# rl78l1a_smart_blood_pressure_monitor_sch.net
KiCad netlist of a schematic drawn in Altium Designer
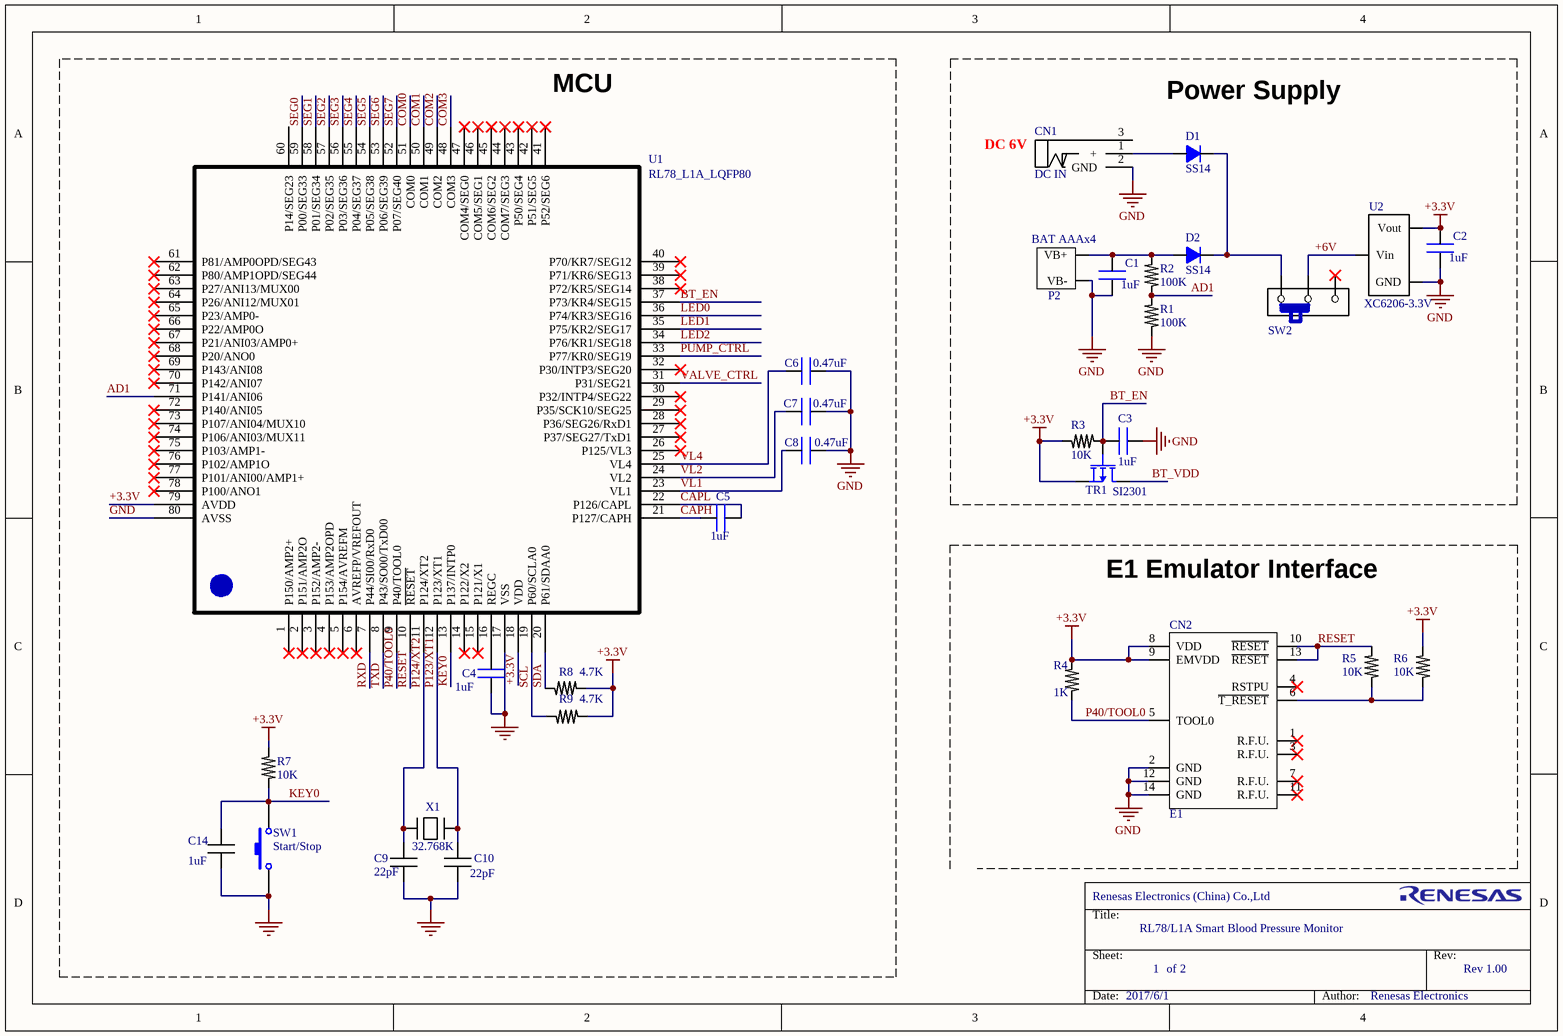
[diagram p0: rl78l1a_smart_blood_pressure_monitor_sch1.SchDoc]

(export (version "E")
  (design (tool "Eeschema 10.0.6"))
  (components
    (comp (ref "C1") (value "1uF") (footprint "0603") (libsource (lib "分立元件") (part "CAP")))
    (comp (ref "C2") (value "1uF") (footprint "0603") (libsource (lib "分立元件") (part "CAP")))
    (comp (ref "C3") (value "1uF") (footprint "0603") (libsource (lib "分立元件") (part "CAP")))
    (comp (ref "C4") (value "1uF") (footprint "0603") (libsource (lib "分立元件") (part "CAP")))
    (comp (ref "C5") (value "1uF") (footprint "0805") (libsource (lib "分立元件") (part "CAP")))
    (comp (ref "C6") (value "0.47uF") (footprint "0805") (libsource (lib "分立元件") (part "CAP")))
    (comp (ref "C7") (value "0.47uF") (footprint "0805") (libsource (lib "分立元件") (part "CAP")))
    (comp (ref "C8") (value "0.47uF") (footprint "0805") (libsource (lib "分立元件") (part "CAP")))
    (comp (ref "C9") (value "22pF") (footprint "0805") (libsource (lib "*") (part "CAP")))
    (comp (ref "C10") (value "22pF") (footprint "0805") (libsource (lib "*") (part "CAP")))
    (comp (ref "C14") (value "1uF") (footprint "0603") (libsource (lib "*") (part "CAP")))
    (comp (ref "CN1") (value "DC IN") (footprint "POWER IN A") (libsource (lib "*") (part "DC IN")))
    (comp (ref "D1") (value "SS14") (footprint "D1N") (libsource (lib "分立元件") (part "1SS404")))
    (comp (ref "D2") (value "SS14") (footprint "D1N") (libsource (lib "分立元件") (part "1SS404")))
    (comp (ref "E1") (value "CN2") (footprint "E8 Connect") (libsource (lib "PCB_Project1") (part "E1")))
    (comp (ref "P2")
      (value "BAT AAAx4")
      (footprint "CON-2MM-2")
      (description "Header, 4-Pin")
      (fields (field (name "PUBLISHER") "Altium Limited"))
      (libsource (lib "*") (part "Cell Battery"))
    )
    (comp (ref "R1") (value "100K") (footprint "0603") (libsource (lib "*") (part "RES")))
    (comp (ref "R2") (value "100K") (footprint "0603") (libsource (lib "*") (part "RES")))
    (comp (ref "R3") (value "10K") (footprint "0603") (libsource (lib "*") (part "RES")))
    (comp (ref "R4") (value "1K") (footprint "0603") (libsource (lib "*") (part "RES")))
    (comp (ref "R5") (value "10K") (footprint "0603") (libsource (lib "*") (part "RES")))
    (comp (ref "R6") (value "10K") (footprint "0603") (libsource (lib "*") (part "RES")))
    (comp (ref "R7") (value "10K") (footprint "0603") (libsource (lib "*") (part "RES")))
    (comp (ref "R8") (value "4.7K") (footprint "0603") (libsource (lib "*") (part "RES")))
    (comp (ref "R9") (value "4.7K") (footprint "0603") (libsource (lib "*") (part "RES")))
    (comp (ref "SW1")
      (value "Start/Stop")
      (footprint "KEY SMT (6 X 6)")
      (description "Switch")
      (fields (field (name "PUBLISHER") "Altium Limited"))
      (libsource (lib "Miscellaneous Devices") (part "SW-PB"))
    )
    (comp (ref "SW2") (value "SWITCH") (footprint "SW-1 C") (libsource (lib "按键") (part "SWITCH")))
    (comp (ref "TR1") (value "SI2301") (footprint "SOT-23-3 B") (libsource (lib "MyPCBLib") (part "PL2301")))
    (comp (ref "U1")
      (value "RL78_L1A_LQFP80")
      (footprint "LQFP-80")
      (libsource (lib "RL78_L1A EVA Board") (part "RL78_L1A_LQFP80"))
    )
    (comp (ref "U2") (value "XC6206-3.3V") (footprint "SOT23A") (libsource (lib "*") (part "XC6206")))
    (comp (ref "X1") (value "32.768K") (footprint "OSC 32K SMT") (libsource (lib "*") (part "OSC 2PIN")))
  )
  (nets
    (net (code "1") (name "+3.3V") (class "Default")
      (node (ref "C2") (pin "1") (pinfunction "1_1") (pintype "passive"))
      (node (ref "E1") (pin "8") (pinfunction "VDD_8") (pintype "passive"))
      (node (ref "E1") (pin "9") (pinfunction "EMVDD_9") (pintype "passive"))
      (node (ref "R3") (pin "1") (pinfunction "1_1") (pintype "passive"))
      (node (ref "R4") (pin "1") (pinfunction "1_1") (pintype "passive"))
      (node (ref "R6") (pin "1") (pinfunction "1_1") (pintype "passive"))
      (node (ref "R7") (pin "2") (pinfunction "2_2") (pintype "passive"))
      (node (ref "R8") (pin "2") (pinfunction "2_2") (pintype "passive"))
      (node (ref "R9") (pin "2") (pinfunction "2_2") (pintype "passive"))
      (node (ref "TR1") (pin "2") (pinfunction "S_2") (pintype "passive"))
      (node (ref "U1") (pin "18") (pinfunction "VDD_18") (pintype "passive"))
      (node (ref "U1") (pin "79") (pinfunction "AVDD_79") (pintype "passive"))
      (node (ref "U2") (pin "2") (pinfunction "Vout_2") (pintype "passive"))
    )
    (net (code "2") (name "/+6V") (class "Default")
      (node (ref "SW2") (pin "2") (pinfunction "2_2") (pintype "passive"))
      (node (ref "U2") (pin "3") (pinfunction "Vin_3") (pintype "passive"))
    )
    (net (code "3") (name "/AD1") (class "Default")
      (node (ref "R1") (pin "2") (pinfunction "2_2") (pintype "passive"))
      (node (ref "R2") (pin "1") (pinfunction "1_1") (pintype "passive"))
      (node (ref "U1") (pin "71") (pinfunction "P141/ANI06_71") (pintype "passive"))
    )
    (net (code "4") (name "/BT_EN") (class "Default")
      (node (ref "C3") (pin "1") (pinfunction "1_1") (pintype "passive"))
      (node (ref "R3") (pin "2") (pinfunction "2_2") (pintype "passive"))
      (node (ref "TR1") (pin "1") (pinfunction "G_1") (pintype "passive"))
      (node (ref "U1") (pin "37") (pinfunction "P73/KR4/SEG15_37") (pintype "passive"))
    )
    (net (code "5") (name "/BT_VDD") (class "Default")
      (node (ref "TR1") (pin "3") (pinfunction "D_3") (pintype "passive"))
    )
    (net (code "6") (name "/CAPH") (class "Default")
      (node (ref "C5") (pin "1") (pinfunction "1_1") (pintype "passive"))
      (node (ref "U1") (pin "21") (pinfunction "P127/CAPH_21") (pintype "passive"))
    )
    (net (code "7") (name "/CAPL") (class "Default")
      (node (ref "C5") (pin "2") (pinfunction "2_2") (pintype "passive"))
      (node (ref "U1") (pin "22") (pinfunction "P126/CAPL_22") (pintype "passive"))
    )
    (net (code "8") (name "/COM0") (class "Default")
      (node (ref "U1") (pin "51") (pinfunction "COM0_51") (pintype "passive"))
    )
    (net (code "9") (name "/COM1") (class "Default")
      (node (ref "U1") (pin "50") (pinfunction "COM1_50") (pintype "passive"))
    )
    (net (code "10") (name "/COM2") (class "Default")
      (node (ref "U1") (pin "49") (pinfunction "COM2_49") (pintype "passive"))
    )
    (net (code "11") (name "/COM3") (class "Default")
      (node (ref "U1") (pin "48") (pinfunction "COM3_48") (pintype "passive"))
    )
    (net (code "12") (name "/KEY0") (class "Default")
      (node (ref "C14") (pin "2") (pinfunction "2_2") (pintype "passive"))
      (node (ref "R7") (pin "1") (pinfunction "1_1") (pintype "passive"))
      (node (ref "SW1") (pin "2") (pinfunction "2_2") (pintype "passive"))
      (node (ref "U1") (pin "13") (pinfunction "P137/INTP0_13") (pintype "passive"))
    )
    (net (code "13") (name "/LED0") (class "Default")
      (node (ref "U1") (pin "36") (pinfunction "P74/KR3/SEG16_36") (pintype "passive"))
    )
    (net (code "14") (name "/LED1") (class "Default")
      (node (ref "U1") (pin "35") (pinfunction "P75/KR2/SEG17_35") (pintype "passive"))
    )
    (net (code "15") (name "/LED2") (class "Default")
      (node (ref "U1") (pin "34") (pinfunction "P76/KR1/SEG18_34") (pintype "passive"))
    )
    (net (code "16") (name "/P40{slash}TOOL0") (class "Default")
      (node (ref "E1") (pin "5") (pinfunction "TOOL0_5") (pintype "passive"))
      (node (ref "R4") (pin "2") (pinfunction "2_2") (pintype "passive"))
      (node (ref "U1") (pin "9") (pinfunction "P40/TOOL0_9") (pintype "passive"))
    )
    (net (code "17") (name "/P123{slash}XT1") (class "Default")
      (node (ref "C10") (pin "2") (pinfunction "2_2") (pintype "passive"))
      (node (ref "U1") (pin "12") (pinfunction "P123/XT1_12") (pintype "passive"))
      (node (ref "X1") (pin "1") (pinfunction "1_1") (pintype "passive"))
    )
    (net (code "18") (name "/P124{slash}XT2") (class "Default")
      (node (ref "C9") (pin "2") (pinfunction "2_2") (pintype "passive"))
      (node (ref "U1") (pin "11") (pinfunction "P124/XT2_11") (pintype "passive"))
      (node (ref "X1") (pin "2") (pinfunction "2_2") (pintype "passive"))
    )
    (net (code "19") (name "/PUMP_CTRL") (class "Default")
      (node (ref "U1") (pin "33") (pinfunction "P77/KR0/SEG19_33") (pintype "passive"))
    )
    (net (code "20") (name "/RESET") (class "Default")
      (node (ref "E1") (pin "10") (pinfunction "~{RESET}_10") (pintype "passive"))
      (node (ref "E1") (pin "13") (pinfunction "~{RESET}_13") (pintype "passive"))
      (node (ref "R5") (pin "1") (pinfunction "1_1") (pintype "passive"))
      (node (ref "U1") (pin "10") (pinfunction "~{RESET}_10") (pintype "passive"))
    )
    (net (code "21") (name "/RXD") (class "Default")
      (node (ref "U1") (pin "7") (pinfunction "P44/SI00/RxD0_7") (pintype "passive"))
    )
    (net (code "22") (name "/SCL") (class "Default")
      (node (ref "R9") (pin "1") (pinfunction "1_1") (pintype "passive"))
      (node (ref "U1") (pin "19") (pinfunction "P60/SCLA0_19") (pintype "passive"))
    )
    (net (code "23") (name "/SDA") (class "Default")
      (node (ref "R8") (pin "1") (pinfunction "1_1") (pintype "passive"))
      (node (ref "U1") (pin "20") (pinfunction "P61/SDAA0_20") (pintype "passive"))
    )
    (net (code "24") (name "/SEG0") (class "Default")
      (node (ref "U1") (pin "59") (pinfunction "P00/SEG33_59") (pintype "passive"))
    )
    (net (code "25") (name "/SEG1") (class "Default")
      (node (ref "U1") (pin "58") (pinfunction "P01/SEG34_58") (pintype "passive"))
    )
    (net (code "26") (name "/SEG2") (class "Default")
      (node (ref "U1") (pin "57") (pinfunction "P02/SEG35_57") (pintype "passive"))
    )
    (net (code "27") (name "/SEG3") (class "Default")
      (node (ref "U1") (pin "56") (pinfunction "P03/SEG36_56") (pintype "passive"))
    )
    (net (code "28") (name "/SEG4") (class "Default")
      (node (ref "U1") (pin "55") (pinfunction "P04/SEG37_55") (pintype "passive"))
    )
    (net (code "29") (name "/SEG5") (class "Default")
      (node (ref "U1") (pin "54") (pinfunction "P05/SEG38_54") (pintype "passive"))
    )
    (net (code "30") (name "/SEG6") (class "Default")
      (node (ref "U1") (pin "53") (pinfunction "P06/SEG39_53") (pintype "passive"))
    )
    (net (code "31") (name "/SEG7") (class "Default")
      (node (ref "U1") (pin "52") (pinfunction "P07/SEG40_52") (pintype "passive"))
    )
    (net (code "32") (name "/TXD") (class "Default")
      (node (ref "U1") (pin "8") (pinfunction "P43/SO00/TxD00_8") (pintype "passive"))
    )
    (net (code "33") (name "/VALVE_CTRL") (class "Default")
      (node (ref "U1") (pin "31") (pinfunction "P31/SEG21_31") (pintype "passive"))
    )
    (net (code "34") (name "/VL1") (class "Default")
      (node (ref "C8") (pin "1") (pinfunction "1_1") (pintype "passive"))
      (node (ref "U1") (pin "23") (pinfunction "VL1_23") (pintype "passive"))
    )
    (net (code "35") (name "/VL2") (class "Default")
      (node (ref "C7") (pin "1") (pinfunction "1_1") (pintype "passive"))
      (node (ref "U1") (pin "24") (pinfunction "VL2_24") (pintype "passive"))
    )
    (net (code "36") (name "/VL4") (class "Default")
      (node (ref "C6") (pin "1") (pinfunction "1_1") (pintype "passive"))
      (node (ref "U1") (pin "25") (pinfunction "VL4_25") (pintype "passive"))
    )
    (net (code "37") (name "GND") (class "Default")
      (node (ref "C1") (pin "2") (pinfunction "2_2") (pintype "passive"))
      (node (ref "C10") (pin "1") (pinfunction "1_1") (pintype "passive"))
      (node (ref "C14") (pin "1") (pinfunction "1_1") (pintype "passive"))
      (node (ref "C2") (pin "2") (pinfunction "2_2") (pintype "passive"))
      (node (ref "C3") (pin "2") (pinfunction "2_2") (pintype "passive"))
      (node (ref "C4") (pin "2") (pinfunction "2_2") (pintype "passive"))
      (node (ref "C6") (pin "2") (pinfunction "2_2") (pintype "passive"))
      (node (ref "C7") (pin "2") (pinfunction "2_2") (pintype "passive"))
      (node (ref "C8") (pin "2") (pinfunction "2_2") (pintype "passive"))
      (node (ref "C9") (pin "1") (pinfunction "1_1") (pintype "passive"))
      (node (ref "CN1") (pin "2") (pinfunction "GND_2") (pintype "passive"))
      (node (ref "E1") (pin "12") (pinfunction "GND_12") (pintype "passive"))
      (node (ref "E1") (pin "14") (pinfunction "GND_14") (pintype "passive"))
      (node (ref "E1") (pin "2") (pinfunction "GND_2") (pintype "passive"))
      (node (ref "P2") (pin "2") (pinfunction "VB-_2") (pintype "passive"))
      (node (ref "R1") (pin "1") (pinfunction "1_1") (pintype "passive"))
      (node (ref "SW1") (pin "1") (pinfunction "1_1") (pintype "passive"))
      (node (ref "U1") (pin "17") (pinfunction "VSS_17") (pintype "passive"))
      (node (ref "U1") (pin "80") (pinfunction "AVSS_80") (pintype "passive"))
      (node (ref "U2") (pin "1") (pinfunction "GND_1") (pintype "passive"))
    )
    (net (code "38") (name "Net-(CN1-+)") (class "Default")
      (node (ref "CN1") (pin "1") (pinfunction "+_1") (pintype "passive"))
      (node (ref "D1") (pin "A") (pinfunction "A_A") (pintype "passive"))
    )
    (net (code "39") (name "Net-(D1-PadK)") (class "Default")
      (node (ref "D1") (pin "K") (pinfunction "K_K") (pintype "passive"))
      (node (ref "D2") (pin "K") (pinfunction "K_K") (pintype "passive"))
      (node (ref "SW2") (pin "1") (pinfunction "1_1") (pintype "passive"))
    )
    (net (code "40") (name "Net-(E1-~{T_RESET})") (class "Default")
      (node (ref "E1") (pin "6") (pinfunction "~{T_RESET}_6") (pintype "passive"))
      (node (ref "R5") (pin "2") (pinfunction "2_2") (pintype "passive"))
      (node (ref "R6") (pin "2") (pinfunction "2_2") (pintype "passive"))
    )
    (net (code "41") (name "Net-(P2-VB+)") (class "Default")
      (node (ref "C1") (pin "1") (pinfunction "1_1") (pintype "passive"))
      (node (ref "D2") (pin "A") (pinfunction "A_A") (pintype "passive"))
      (node (ref "P2") (pin "1") (pinfunction "VB+_1") (pintype "passive"))
      (node (ref "R2") (pin "2") (pinfunction "2_2") (pintype "passive"))
    )
    (net (code "42") (name "Net-(U1-REGC)") (class "Default")
      (node (ref "C4") (pin "1") (pinfunction "1_1") (pintype "passive"))
      (node (ref "U1") (pin "16") (pinfunction "REGC_16") (pintype "passive"))
    )
    (net (code "43") (name "unconnected-(CN1-C-Pad3)") (class "Default")
      (node (ref "CN1") (pin "3") (pinfunction "C_3") (pintype "passive"))
    )
    (net (code "44") (name "unconnected-(E1-R.F.U.-Pad1)") (class "Default")
      (node (ref "E1") (pin "1") (pinfunction "R.F.U._1") (pintype "passive+no_connect"))
    )
    (net (code "45") (name "unconnected-(E1-R.F.U.-Pad3)") (class "Default")
      (node (ref "E1") (pin "3") (pinfunction "R.F.U._3") (pintype "passive+no_connect"))
    )
    (net (code "46") (name "unconnected-(E1-R.F.U.-Pad7)") (class "Default")
      (node (ref "E1") (pin "7") (pinfunction "R.F.U._7") (pintype "passive+no_connect"))
    )
    (net (code "47") (name "unconnected-(E1-R.F.U.-Pad11)") (class "Default")
      (node (ref "E1") (pin "11") (pinfunction "R.F.U._11") (pintype "passive+no_connect"))
    )
    (net (code "48") (name "unconnected-(E1-RSTPU-Pad4)") (class "Default")
      (node (ref "E1") (pin "4") (pinfunction "RSTPU_4") (pintype "passive+no_connect"))
    )
    (net (code "49") (name "unconnected-(SW2-Pad3)") (class "Default")
      (node (ref "SW2") (pin "3") (pinfunction "3_3") (pintype "passive+no_connect"))
    )
    (net (code "50") (name "unconnected-(U1-AVREFP{slash}VREFOUT-Pad6)") (class "Default")
      (node (ref "U1") (pin "6") (pinfunction "AVREFP/VREFOUT_6") (pintype "passive+no_connect"))
    )
    (net (code "51") (name "unconnected-(U1-COM4{slash}SEG0-Pad47)") (class "Default")
      (node (ref "U1") (pin "47") (pinfunction "COM4/SEG0_47") (pintype "passive+no_connect"))
    )
    (net (code "52") (name "unconnected-(U1-COM5{slash}SEG1-Pad46)") (class "Default")
      (node (ref "U1") (pin "46") (pinfunction "COM5/SEG1_46") (pintype "passive+no_connect"))
    )
    (net (code "53") (name "unconnected-(U1-COM6{slash}SEG2-Pad45)") (class "Default")
      (node (ref "U1") (pin "45") (pinfunction "COM6/SEG2_45") (pintype "passive+no_connect"))
    )
    (net (code "54") (name "unconnected-(U1-COM7{slash}SEG3-Pad44)") (class "Default")
      (node (ref "U1") (pin "44") (pinfunction "COM7/SEG3_44") (pintype "passive+no_connect"))
    )
    (net (code "55") (name "unconnected-(U1-P14{slash}SEG23-Pad60)") (class "Default")
      (node (ref "U1") (pin "60") (pinfunction "P14/SEG23_60") (pintype "passive"))
    )
    (net (code "56") (name "unconnected-(U1-P20{slash}ANO0-Pad68)") (class "Default")
      (node (ref "U1") (pin "68") (pinfunction "P20/ANO0_68") (pintype "passive+no_connect"))
    )
    (net (code "57") (name "unconnected-(U1-P21{slash}ANI03{slash}AMP0+-Pad67)") (class "Default")
      (node (ref "U1") (pin "67") (pinfunction "P21/ANI03/AMP0+_67") (pintype "passive+no_connect"))
    )
    (net (code "58") (name "unconnected-(U1-P22{slash}AMP0O-Pad66)") (class "Default")
      (node (ref "U1") (pin "66") (pinfunction "P22/AMP0O_66") (pintype "passive+no_connect"))
    )
    (net (code "59") (name "unconnected-(U1-P23{slash}AMP0--Pad65)") (class "Default")
      (node (ref "U1") (pin "65") (pinfunction "P23/AMP0-_65") (pintype "passive+no_connect"))
    )
    (net (code "60") (name "unconnected-(U1-P26{slash}ANI12{slash}MUX01-Pad64)") (class "Default")
      (node (ref "U1") (pin "64") (pinfunction "P26/ANI12/MUX01_64") (pintype "passive+no_connect"))
    )
    (net (code "61") (name "unconnected-(U1-P27{slash}ANI13{slash}MUX00-Pad63)") (class "Default")
      (node (ref "U1") (pin "63") (pinfunction "P27/ANI13/MUX00_63") (pintype "passive+no_connect"))
    )
    (net (code "62") (name "unconnected-(U1-P30{slash}INTP3{slash}SEG20-Pad32)") (class "Default")
      (node (ref "U1") (pin "32") (pinfunction "P30/INTP3/SEG20_32") (pintype "passive+no_connect"))
    )
    (net (code "63") (name "unconnected-(U1-P32{slash}INTP4{slash}SEG22-Pad30)") (class "Default")
      (node (ref "U1") (pin "30") (pinfunction "P32/INTP4/SEG22_30") (pintype "passive+no_connect"))
    )
    (net (code "64") (name "unconnected-(U1-P35{slash}SCK10{slash}SEG25-Pad29)") (class "Default")
      (node (ref "U1") (pin "29") (pinfunction "P35/SCK10/SEG25_29") (pintype "passive+no_connect"))
    )
    (net (code "65") (name "unconnected-(U1-P36{slash}SEG26{slash}RxD1-Pad28)") (class "Default")
      (node (ref "U1") (pin "28") (pinfunction "P36/SEG26/RxD1_28") (pintype "passive+no_connect"))
    )
    (net (code "66") (name "unconnected-(U1-P37{slash}SEG27{slash}TxD1-Pad27)") (class "Default")
      (node (ref "U1") (pin "27") (pinfunction "P37/SEG27/TxD1_27") (pintype "passive+no_connect"))
    )
    (net (code "67") (name "unconnected-(U1-P50{slash}SEG4-Pad43)") (class "Default")
      (node (ref "U1") (pin "43") (pinfunction "P50/SEG4_43") (pintype "passive+no_connect"))
    )
    (net (code "68") (name "unconnected-(U1-P51{slash}SEG5-Pad42)") (class "Default")
      (node (ref "U1") (pin "42") (pinfunction "P51/SEG5_42") (pintype "passive+no_connect"))
    )
    (net (code "69") (name "unconnected-(U1-P52{slash}SEG6-Pad41)") (class "Default")
      (node (ref "U1") (pin "41") (pinfunction "P52/SEG6_41") (pintype "passive+no_connect"))
    )
    (net (code "70") (name "unconnected-(U1-P70{slash}KR7{slash}SEG12-Pad40)") (class "Default")
      (node (ref "U1") (pin "40") (pinfunction "P70/KR7/SEG12_40") (pintype "passive+no_connect"))
    )
    (net (code "71") (name "unconnected-(U1-P71{slash}KR6{slash}SEG13-Pad39)") (class "Default")
      (node (ref "U1") (pin "39") (pinfunction "P71/KR6/SEG13_39") (pintype "passive+no_connect"))
    )
    (net (code "72") (name "unconnected-(U1-P72{slash}KR5{slash}SEG14-Pad38)") (class "Default")
      (node (ref "U1") (pin "38") (pinfunction "P72/KR5/SEG14_38") (pintype "passive+no_connect"))
    )
    (net (code "73") (name "unconnected-(U1-P80{slash}AMP1OPD{slash}SEG44-Pad62)") (class "Default")
      (node (ref "U1") (pin "62") (pinfunction "P80/AMP1OPD/SEG44_62") (pintype "passive+no_connect"))
    )
    (net (code "74") (name "unconnected-(U1-P81{slash}AMP0OPD{slash}SEG43-Pad61)") (class "Default")
      (node (ref "U1") (pin "61") (pinfunction "P81/AMP0OPD/SEG43_61") (pintype "passive+no_connect"))
    )
    (net (code "75") (name "unconnected-(U1-P100{slash}ANO1-Pad78)") (class "Default")
      (node (ref "U1") (pin "78") (pinfunction "P100/ANO1_78") (pintype "passive+no_connect"))
    )
    (net (code "76") (name "unconnected-(U1-P101{slash}ANI00{slash}AMP1+-Pad77)") (class "Default")
      (node (ref "U1") (pin "77") (pinfunction "P101/ANI00/AMP1+_77") (pintype "passive+no_connect"))
    )
    (net (code "77") (name "unconnected-(U1-P102{slash}AMP1O-Pad76)") (class "Default")
      (node (ref "U1") (pin "76") (pinfunction "P102/AMP1O_76") (pintype "passive+no_connect"))
    )
    (net (code "78") (name "unconnected-(U1-P103{slash}AMP1--Pad75)") (class "Default")
      (node (ref "U1") (pin "75") (pinfunction "P103/AMP1-_75") (pintype "passive+no_connect"))
    )
    (net (code "79") (name "unconnected-(U1-P106{slash}ANI03{slash}MUX11-Pad74)") (class "Default")
      (node (ref "U1") (pin "74") (pinfunction "P106/ANI03/MUX11_74") (pintype "passive+no_connect"))
    )
    (net (code "80") (name "unconnected-(U1-P107{slash}ANI04{slash}MUX10-Pad73)") (class "Default")
      (node (ref "U1") (pin "73") (pinfunction "P107/ANI04/MUX10_73") (pintype "passive+no_connect"))
    )
    (net (code "81") (name "unconnected-(U1-P121{slash}X1-Pad15)") (class "Default")
      (node (ref "U1") (pin "15") (pinfunction "P121/X1_15") (pintype "passive+no_connect"))
    )
    (net (code "82") (name "unconnected-(U1-P122{slash}X2-Pad14)") (class "Default")
      (node (ref "U1") (pin "14") (pinfunction "P122/X2_14") (pintype "passive+no_connect"))
    )
    (net (code "83") (name "unconnected-(U1-P125{slash}VL3-Pad26)") (class "Default")
      (node (ref "U1") (pin "26") (pinfunction "P125/VL3_26") (pintype "passive+no_connect"))
    )
    (net (code "84") (name "unconnected-(U1-P140{slash}ANI05-Pad72)") (class "Default")
      (node (ref "U1") (pin "72") (pinfunction "P140/ANI05_72") (pintype "passive+no_connect"))
    )
    (net (code "85") (name "unconnected-(U1-P142{slash}ANI07-Pad70)") (class "Default")
      (node (ref "U1") (pin "70") (pinfunction "P142/ANI07_70") (pintype "passive+no_connect"))
    )
    (net (code "86") (name "unconnected-(U1-P143{slash}ANI08-Pad69)") (class "Default")
      (node (ref "U1") (pin "69") (pinfunction "P143/ANI08_69") (pintype "passive+no_connect"))
    )
    (net (code "87") (name "unconnected-(U1-P150{slash}AMP2+-Pad1)") (class "Default")
      (node (ref "U1") (pin "1") (pinfunction "P150/AMP2+_1") (pintype "passive+no_connect"))
    )
    (net (code "88") (name "unconnected-(U1-P151{slash}AMP2O-Pad2)") (class "Default")
      (node (ref "U1") (pin "2") (pinfunction "P151/AMP2O_2") (pintype "passive+no_connect"))
    )
    (net (code "89") (name "unconnected-(U1-P152{slash}AMP2--Pad3)") (class "Default")
      (node (ref "U1") (pin "3") (pinfunction "P152/AMP2-_3") (pintype "passive+no_connect"))
    )
    (net (code "90") (name "unconnected-(U1-P153{slash}AMP2OPD-Pad4)") (class "Default")
      (node (ref "U1") (pin "4") (pinfunction "P153/AMP2OPD_4") (pintype "passive+no_connect"))
    )
    (net (code "91") (name "unconnected-(U1-P154{slash}AVREFM-Pad5)") (class "Default")
      (node (ref "U1") (pin "5") (pinfunction "P154/AVREFM_5") (pintype "passive+no_connect"))
    )
  )
)
